# ControlledCharger.net
KiCad netlist of a schematic drawn in Altium Designer
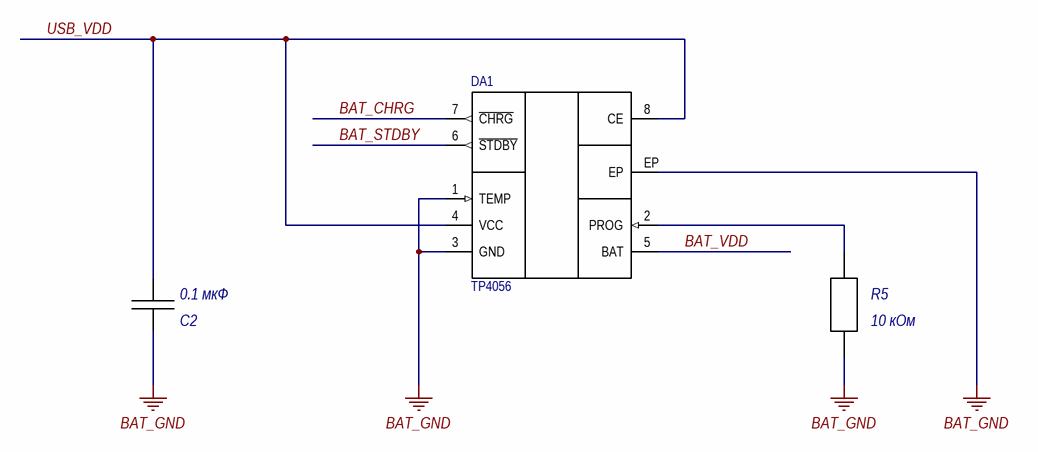
[diagram p0: ControlledCharger.SchDoc]

(export (version "E")
  (design (tool "Eeschema 10.0.6"))
  (components
    (comp (ref "C2")
      (value "0.1 мкФ")
      (footprint "C 0805")
      (description "SMD Capacitor 0805")
      (fields
        (field (name "TOLERANCE") "/Укажите допуск в процентах/")
        (field (name "MANUFACTURER") "/Укажите компанию-производителя/")
      )
      (libsource (lib "my_lib") (part "CAP 0805"))
    )
    (comp (ref "DA1") (value "TP4056") (footprint "HSOP-8") (libsource (lib "my_lib") (part "TP4056")))
    (comp (ref "R5") (value "10 кОм") (footprint "RES 0402") (libsource (lib "my_lib") (part "RES 0402")))
  )
  (nets
    (net (code "1") (name "/BAT_CHRG") (class "Default")
      (node (ref "DA1") (pin "7") (pinfunction "~{CHRG}_7") (pintype "output"))
    )
    (net (code "2") (name "/BAT_STDBY") (class "Default")
      (node (ref "DA1") (pin "6") (pinfunction "~{STDBY}_6") (pintype "output"))
    )
    (net (code "3") (name "/BAT_VDD") (class "Default")
      (node (ref "DA1") (pin "5") (pinfunction "BAT_5") (pintype "power_in"))
    )
    (net (code "4") (name "/USB_VDD") (class "Default")
      (node (ref "C2") (pin "1") (pinfunction "1_1") (pintype "passive"))
      (node (ref "DA1") (pin "4") (pinfunction "VCC_4") (pintype "power_in"))
      (node (ref "DA1") (pin "8") (pinfunction "CE_8") (pintype "passive"))
    )
    (net (code "5") (name "BAT_GND") (class "Default")
      (node (ref "C2") (pin "2") (pinfunction "2_2") (pintype "passive"))
      (node (ref "DA1") (pin "1") (pinfunction "TEMP_1") (pintype "input"))
      (node (ref "DA1") (pin "3") (pinfunction "GND_3") (pintype "power_in"))
      (node (ref "DA1") (pin "EP") (pinfunction "EP_EP") (pintype "passive"))
      (node (ref "R5") (pin "1") (pinfunction "1_1") (pintype "passive"))
    )
    (net (code "6") (name "Net-(DA1-PROG)") (class "Default")
      (node (ref "DA1") (pin "2") (pinfunction "PROG_2") (pintype "input"))
      (node (ref "R5") (pin "2") (pinfunction "2_2") (pintype "passive"))
    )
  )
)
